# WIFI.net
KiCad netlist of a schematic drawn in Altium Designer
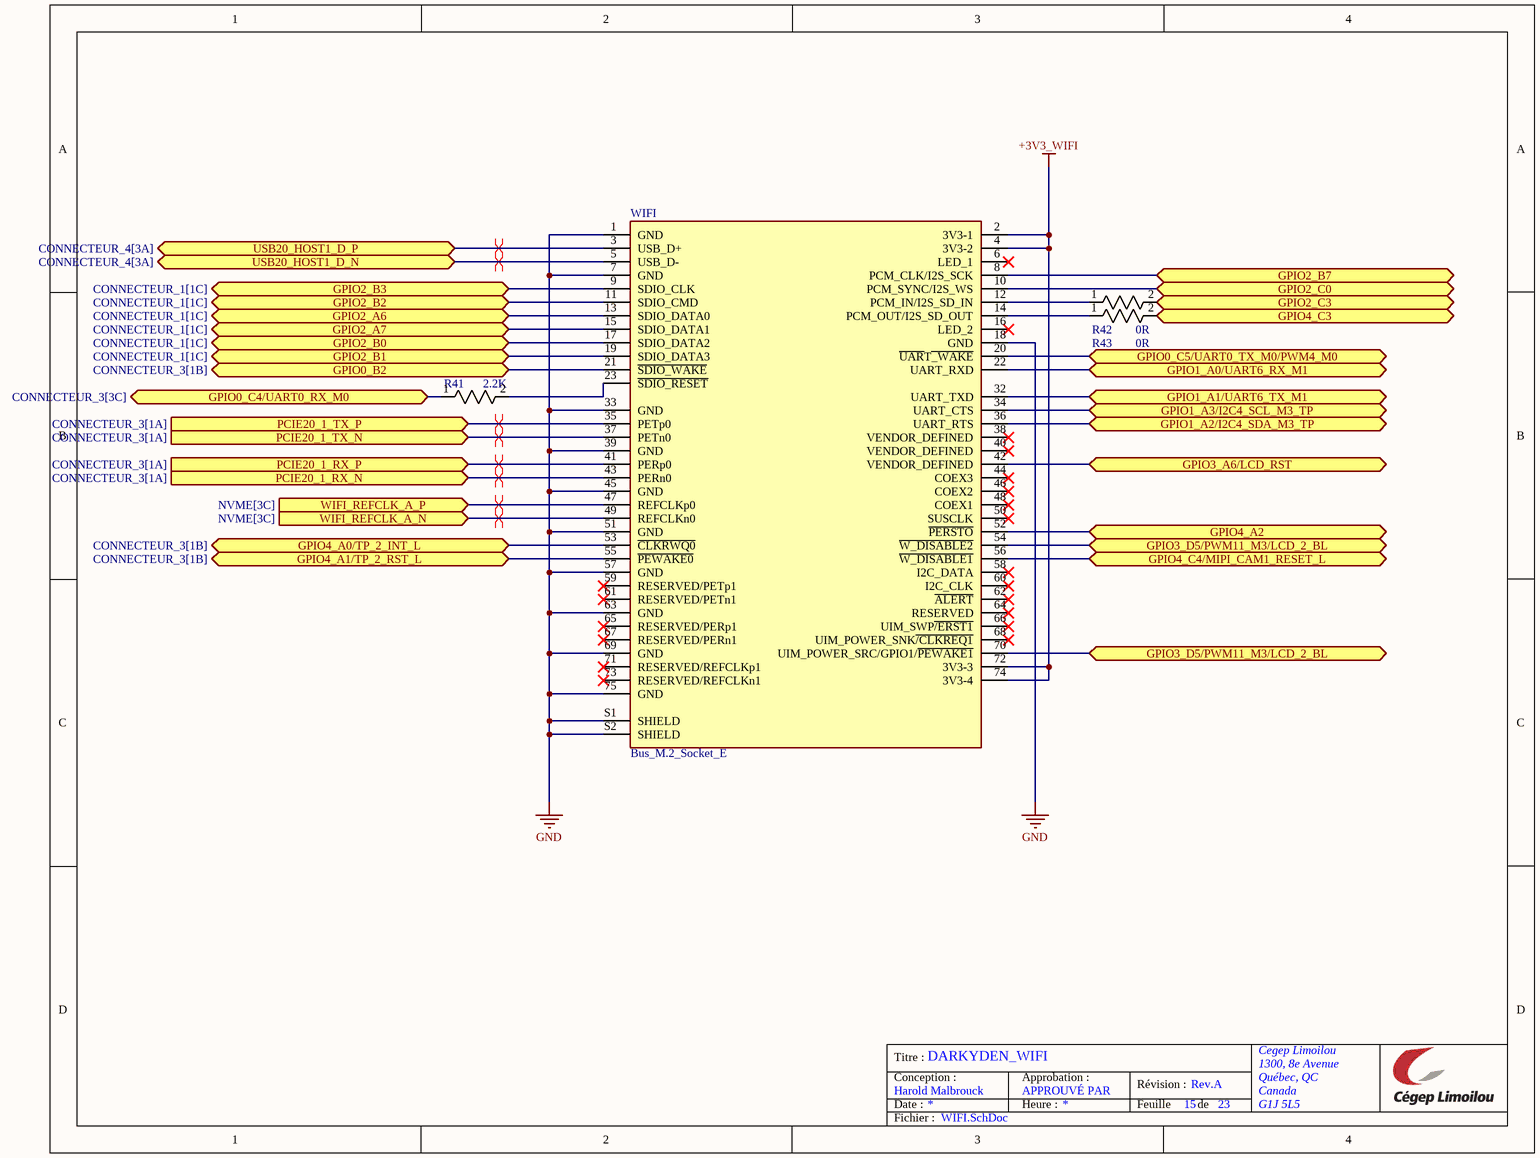
[diagram p0: WIFI.SchDoc]

(export (version "E")
  (design (tool "Eeschema 10.0.6"))
  (components
    (comp (ref "R41")
      (value "2.2K")
      (footprint "SamacSys:RESC1608X55N")
      (description "2.2 kOhm, ï¿½ 5%, 100 mW, 0603 [1608 Metric], Thick Film, General Purpose")
      (fields
        (field (name "MANUFACTURER_PART_NUMBER") "ERJ-3GEYJ222V")
        (field (name "MOUSER PART NUMBER") "667-ERJ-3GEYJ222V")
      )
      (libsource (lib "DARKYDEN") (part "ERJ-3GEYJ222V"))
    )
    (comp (ref "R42")
      (value "0R")
      (footprint "SamacSys:RESC1608X55N")
      (description "Zero Ohm Resistor, Jumper, 0603 [1608 Metric], Thick Film, 100 mW, 1 A, Surface Mount")
      (fields
        (field (name "MANUFACTURER_PART_NUMBER") "ERJ-3GEY0R00V")
        (field (name "MOUSER PART NUMBER") "667-ERJ-3GEY0R00V")
      )
      (libsource (lib "DARKYDEN") (part "ERJ-3GEY0R00V"))
    )
    (comp (ref "R43")
      (value "0R")
      (footprint "SamacSys:RESC1608X55N")
      (description "Zero Ohm Resistor, Jumper, 0603 [1608 Metric], Thick Film, 100 mW, 1 A, Surface Mount")
      (fields
        (field (name "MANUFACTURER_PART_NUMBER") "ERJ-3GEY0R00V")
        (field (name "MOUSER PART NUMBER") "667-ERJ-3GEY0R00V")
      )
      (libsource (lib "DARKYDEN") (part "ERJ-3GEY0R00V"))
    )
    (comp (ref "WIFI")
      (value "Bus_M.2_Socket_E")
      (footprint "AMPHENOL_MDT320E01001")
      (description "PCIe M.2 Connectors, Storage and Server Connector, P=0.5mm, H=3.2mm, Key E,30Î¼in Au Plating")
      (fields (field (name "MP") "MDT320E01001") (field (name "MF") "Amphenol ICC"))
      (libsource (lib "Bus_M.2_Socket_E") (part "Bus_M.2_Socket_E"))
    )
  )
  (nets
    (net (code "1") (name "+3V3_WIFI") (class "Default")
      (node (ref "WIFI") (pin "2") (pinfunction "3V3-1_2") (pintype "power_in"))
      (node (ref "WIFI") (pin "4") (pinfunction "3V3-2_4") (pintype "power_in"))
      (node (ref "WIFI") (pin "72") (pinfunction "3V3-3_72") (pintype "power_in"))
      (node (ref "WIFI") (pin "74") (pinfunction "3V3-4_74") (pintype "power_in"))
    )
    (net (code "2") (name "/GPIO0_B2") (class "Default")
      (node (ref "WIFI") (pin "21") (pinfunction "~{SDIO_WAKE}_21") (pintype "passive"))
    )
    (net (code "3") (name "/GPIO0_C4{slash}UART0_RX_M0") (class "Default")
      (node (ref "R41") (pin "1") (pinfunction "1_1") (pintype "passive"))
    )
    (net (code "4") (name "/GPIO0_C5{slash}UART0_TX_M0{slash}PWM4_M0") (class "Default")
      (node (ref "WIFI") (pin "20") (pinfunction "~{UAR}T~{_WAKE}_20") (pintype "passive"))
    )
    (net (code "5") (name "/GPIO1_A0{slash}UART6_RX_M1") (class "Default")
      (node (ref "WIFI") (pin "22") (pinfunction "UART_RXD_22") (pintype "passive"))
    )
    (net (code "6") (name "/GPIO1_A1{slash}UART6_TX_M1") (class "Default")
      (node (ref "WIFI") (pin "32") (pinfunction "UART_TXD_32") (pintype "passive"))
    )
    (net (code "7") (name "/GPIO1_A2{slash}I2C4_SDA_M3_TP") (class "Default")
      (node (ref "WIFI") (pin "36") (pinfunction "UART_RTS_36") (pintype "passive"))
    )
    (net (code "8") (name "/GPIO1_A3{slash}I2C4_SCL_M3_TP") (class "Default")
      (node (ref "WIFI") (pin "34") (pinfunction "UART_CTS_34") (pintype "passive"))
    )
    (net (code "9") (name "/GPIO2_A6") (class "Default")
      (node (ref "WIFI") (pin "13") (pinfunction "SDIO_DATA0_13") (pintype "passive"))
    )
    (net (code "10") (name "/GPIO2_A7") (class "Default")
      (node (ref "WIFI") (pin "15") (pinfunction "SDIO_DATA1_15") (pintype "passive"))
    )
    (net (code "11") (name "/GPIO2_B0") (class "Default")
      (node (ref "WIFI") (pin "17") (pinfunction "SDIO_DATA2_17") (pintype "passive"))
    )
    (net (code "12") (name "/GPIO2_B1") (class "Default")
      (node (ref "WIFI") (pin "19") (pinfunction "SDIO_DATA3_19") (pintype "passive"))
    )
    (net (code "13") (name "/GPIO2_B2") (class "Default")
      (node (ref "WIFI") (pin "11") (pinfunction "SDIO_CMD_11") (pintype "passive"))
    )
    (net (code "14") (name "/GPIO2_B3") (class "Default")
      (node (ref "WIFI") (pin "9") (pinfunction "SDIO_CLK_9") (pintype "passive"))
    )
    (net (code "15") (name "/GPIO2_B7") (class "Default")
      (node (ref "WIFI") (pin "8") (pinfunction "PCM_CLK/I2S_SCK_8") (pintype "passive"))
    )
    (net (code "16") (name "/GPIO2_C0") (class "Default")
      (node (ref "WIFI") (pin "10") (pinfunction "PCM_SYNC/I2S_WS_10") (pintype "passive"))
    )
    (net (code "17") (name "/GPIO2_C3") (class "Default")
      (node (ref "R42") (pin "2") (pinfunction "2_2") (pintype "passive"))
    )
    (net (code "18") (name "/GPIO3_A6{slash}LCD_RST") (class "Default")
      (node (ref "WIFI") (pin "42") (pinfunction "VENDOR_DEFINED_42") (pintype "passive"))
    )
    (net (code "19") (name "/GPIO3_D5{slash}PWM11_M3{slash}LCD_2_BL") (class "Default")
      (node (ref "WIFI") (pin "54") (pinfunction "~{W_DISABLE2}_54") (pintype "passive"))
      (node (ref "WIFI") (pin "70") (pinfunction "UIM_POWER_SRC/GPIO1/~{PEWAKE1}_70") (pintype "passive"))
    )
    (net (code "20") (name "/GPIO4_A0{slash}TP_2_INT_L") (class "Default")
      (node (ref "WIFI") (pin "53") (pinfunction "~{CLKRWQ0}_53") (pintype "passive"))
    )
    (net (code "21") (name "/GPIO4_A1{slash}TP_2_RST_L") (class "Default")
      (node (ref "WIFI") (pin "55") (pinfunction "~{PEWAKE0}_55") (pintype "passive"))
    )
    (net (code "22") (name "/GPIO4_A2") (class "Default")
      (node (ref "WIFI") (pin "52") (pinfunction "~{PERSTO}_52") (pintype "passive"))
    )
    (net (code "23") (name "/GPIO4_C3") (class "Default")
      (node (ref "R43") (pin "2") (pinfunction "2_2") (pintype "passive"))
    )
    (net (code "24") (name "/GPIO4_C4{slash}MIPI_CAM1_RESET_L") (class "Default")
      (node (ref "WIFI") (pin "56") (pinfunction "~{W_DISABLE1}_56") (pintype "passive"))
    )
    (net (code "25") (name "/PCIE20_1_RX_N") (class "Default")
      (node (ref "WIFI") (pin "43") (pinfunction "PERn0_43") (pintype "passive"))
    )
    (net (code "26") (name "/PCIE20_1_RX_P") (class "Default")
      (node (ref "WIFI") (pin "41") (pinfunction "PERp0_41") (pintype "passive"))
    )
    (net (code "27") (name "/PCIE20_1_TX_N") (class "Default")
      (node (ref "WIFI") (pin "37") (pinfunction "PETn0_37") (pintype "passive"))
    )
    (net (code "28") (name "/PCIE20_1_TX_P") (class "Default")
      (node (ref "WIFI") (pin "35") (pinfunction "PETp0_35") (pintype "passive"))
    )
    (net (code "29") (name "/USB20_HOST1_D_N") (class "Default")
      (node (ref "WIFI") (pin "5") (pinfunction "USB_D-_5") (pintype "passive"))
    )
    (net (code "30") (name "/USB20_HOST1_D_P") (class "Default")
      (node (ref "WIFI") (pin "3") (pinfunction "USB_D+_3") (pintype "passive"))
    )
    (net (code "31") (name "/WIFI_REFCLK_A_N") (class "Default")
      (node (ref "WIFI") (pin "49") (pinfunction "REFCLKn0_49") (pintype "passive"))
    )
    (net (code "32") (name "/WIFI_REFCLK_A_P") (class "Default")
      (node (ref "WIFI") (pin "47") (pinfunction "REFCLKp0_47") (pintype "passive"))
    )
    (net (code "33") (name "GND") (class "Default")
      (node (ref "WIFI") (pin "1") (pinfunction "GND_1") (pintype "passive"))
      (node (ref "WIFI") (pin "18") (pinfunction "GND_18") (pintype "passive"))
      (node (ref "WIFI") (pin "33") (pinfunction "GND_33") (pintype "passive"))
      (node (ref "WIFI") (pin "39") (pinfunction "GND_39") (pintype "passive"))
      (node (ref "WIFI") (pin "45") (pinfunction "GND_45") (pintype "passive"))
      (node (ref "WIFI") (pin "51") (pinfunction "GND_51") (pintype "passive"))
      (node (ref "WIFI") (pin "57") (pinfunction "GND_57") (pintype "passive"))
      (node (ref "WIFI") (pin "63") (pinfunction "GND_63") (pintype "passive"))
      (node (ref "WIFI") (pin "69") (pinfunction "GND_69") (pintype "passive"))
      (node (ref "WIFI") (pin "7") (pinfunction "GND_7") (pintype "passive"))
      (node (ref "WIFI") (pin "75") (pinfunction "GND_75") (pintype "passive"))
      (node (ref "WIFI") (pin "S1") (pinfunction "SHIELD_S1") (pintype "passive"))
      (node (ref "WIFI") (pin "S2") (pinfunction "SHIELD_S2") (pintype "passive"))
    )
    (net (code "34") (name "Net-(WIFI-PCM_IN{slash}I2S_SD_IN)") (class "Default")
      (node (ref "R42") (pin "1") (pinfunction "1_1") (pintype "passive"))
      (node (ref "WIFI") (pin "12") (pinfunction "PCM_IN/I2S_SD_IN_12") (pintype "passive"))
    )
    (net (code "35") (name "Net-(WIFI-PCM_OUT{slash}I2S_SD_OUT)") (class "Default")
      (node (ref "R43") (pin "1") (pinfunction "1_1") (pintype "passive"))
      (node (ref "WIFI") (pin "14") (pinfunction "PCM_OUT/I2S_SD_OUT_14") (pintype "passive"))
    )
    (net (code "36") (name "Net-(WIFI-~{SDIO_RESET})") (class "Default")
      (node (ref "R41") (pin "2") (pinfunction "2_2") (pintype "passive"))
      (node (ref "WIFI") (pin "23") (pinfunction "~{SDIO_RESET}_23") (pintype "passive"))
    )
    (net (code "37") (name "unconnected-(WIFI-COEX1-Pad48)") (class "Default")
      (node (ref "WIFI") (pin "48") (pinfunction "COEX1_48") (pintype "passive+no_connect"))
    )
    (net (code "38") (name "unconnected-(WIFI-COEX2-Pad46)") (class "Default")
      (node (ref "WIFI") (pin "46") (pinfunction "COEX2_46") (pintype "passive+no_connect"))
    )
    (net (code "39") (name "unconnected-(WIFI-COEX3-Pad44)") (class "Default")
      (node (ref "WIFI") (pin "44") (pinfunction "COEX3_44") (pintype "passive+no_connect"))
    )
    (net (code "40") (name "unconnected-(WIFI-I2C_CLK-Pad60)") (class "Default")
      (node (ref "WIFI") (pin "60") (pinfunction "I2C_CLK_60") (pintype "passive+no_connect"))
    )
    (net (code "41") (name "unconnected-(WIFI-I2C_DATA-Pad58)") (class "Default")
      (node (ref "WIFI") (pin "58") (pinfunction "I2C_DATA_58") (pintype "passive+no_connect"))
    )
    (net (code "42") (name "unconnected-(WIFI-LED_1-Pad6)") (class "Default")
      (node (ref "WIFI") (pin "6") (pinfunction "LED_1_6") (pintype "passive+no_connect"))
    )
    (net (code "43") (name "unconnected-(WIFI-LED_2-Pad16)") (class "Default")
      (node (ref "WIFI") (pin "16") (pinfunction "LED_2_16") (pintype "passive+no_connect"))
    )
    (net (code "44") (name "unconnected-(WIFI-RESERVED-Pad64)") (class "Default")
      (node (ref "WIFI") (pin "64") (pinfunction "RESERVED_64") (pintype "passive+no_connect"))
    )
    (net (code "45") (name "unconnected-(WIFI-RESERVED{slash}PERn1-Pad67)") (class "Default")
      (node (ref "WIFI") (pin "67") (pinfunction "RESERVED/PERn1_67") (pintype "passive+no_connect"))
    )
    (net (code "46") (name "unconnected-(WIFI-RESERVED{slash}PERp1-Pad65)") (class "Default")
      (node (ref "WIFI") (pin "65") (pinfunction "RESERVED/PERp1_65") (pintype "passive+no_connect"))
    )
    (net (code "47") (name "unconnected-(WIFI-RESERVED{slash}PETn1-Pad61)") (class "Default")
      (node (ref "WIFI") (pin "61") (pinfunction "RESERVED/PETn1_61") (pintype "passive+no_connect"))
    )
    (net (code "48") (name "unconnected-(WIFI-RESERVED{slash}PETp1-Pad59)") (class "Default")
      (node (ref "WIFI") (pin "59") (pinfunction "RESERVED/PETp1_59") (pintype "passive+no_connect"))
    )
    (net (code "49") (name "unconnected-(WIFI-RESERVED{slash}REFCLKn1-Pad73)") (class "Default")
      (node (ref "WIFI") (pin "73") (pinfunction "RESERVED/REFCLKn1_73") (pintype "passive+no_connect"))
    )
    (net (code "50") (name "unconnected-(WIFI-RESERVED{slash}REFCLKp1-Pad71)") (class "Default")
      (node (ref "WIFI") (pin "71") (pinfunction "RESERVED/REFCLKp1_71") (pintype "passive+no_connect"))
    )
    (net (code "51") (name "unconnected-(WIFI-SUSCLK-Pad50)") (class "Default")
      (node (ref "WIFI") (pin "50") (pinfunction "SUSCLK_50") (pintype "passive+no_connect"))
    )
    (net (code "52") (name "unconnected-(WIFI-UIM_POWER_SNK~{{slash}CLKREQ1}-Pad68)") (class "Default")
      (node (ref "WIFI") (pin "68") (pinfunction "UIM_POWER_SNK~{/CLKREQ1}_68") (pintype "passive+no_connect"))
    )
    (net (code "53") (name "unconnected-(WIFI-UIM_SWP~{{slash}ERST1}-Pad66)") (class "Default")
      (node (ref "WIFI") (pin "66") (pinfunction "UIM_SWP~{/ERST1}_66") (pintype "passive+no_connect"))
    )
    (net (code "54") (name "unconnected-(WIFI-VENDOR_DEFINED-Pad38)") (class "Default")
      (node (ref "WIFI") (pin "38") (pinfunction "VENDOR_DEFINED_38") (pintype "passive+no_connect"))
    )
    (net (code "55") (name "unconnected-(WIFI-VENDOR_DEFINED-Pad40)") (class "Default")
      (node (ref "WIFI") (pin "40") (pinfunction "VENDOR_DEFINED_40") (pintype "passive+no_connect"))
    )
    (net (code "56") (name "unconnected-(WIFI-~{ALERT}-Pad62)") (class "Default")
      (node (ref "WIFI") (pin "62") (pinfunction "~{ALERT}_62") (pintype "passive+no_connect"))
    )
  )
)
